# SOM_USB.net
KiCad netlist of a schematic drawn in Altium Designer
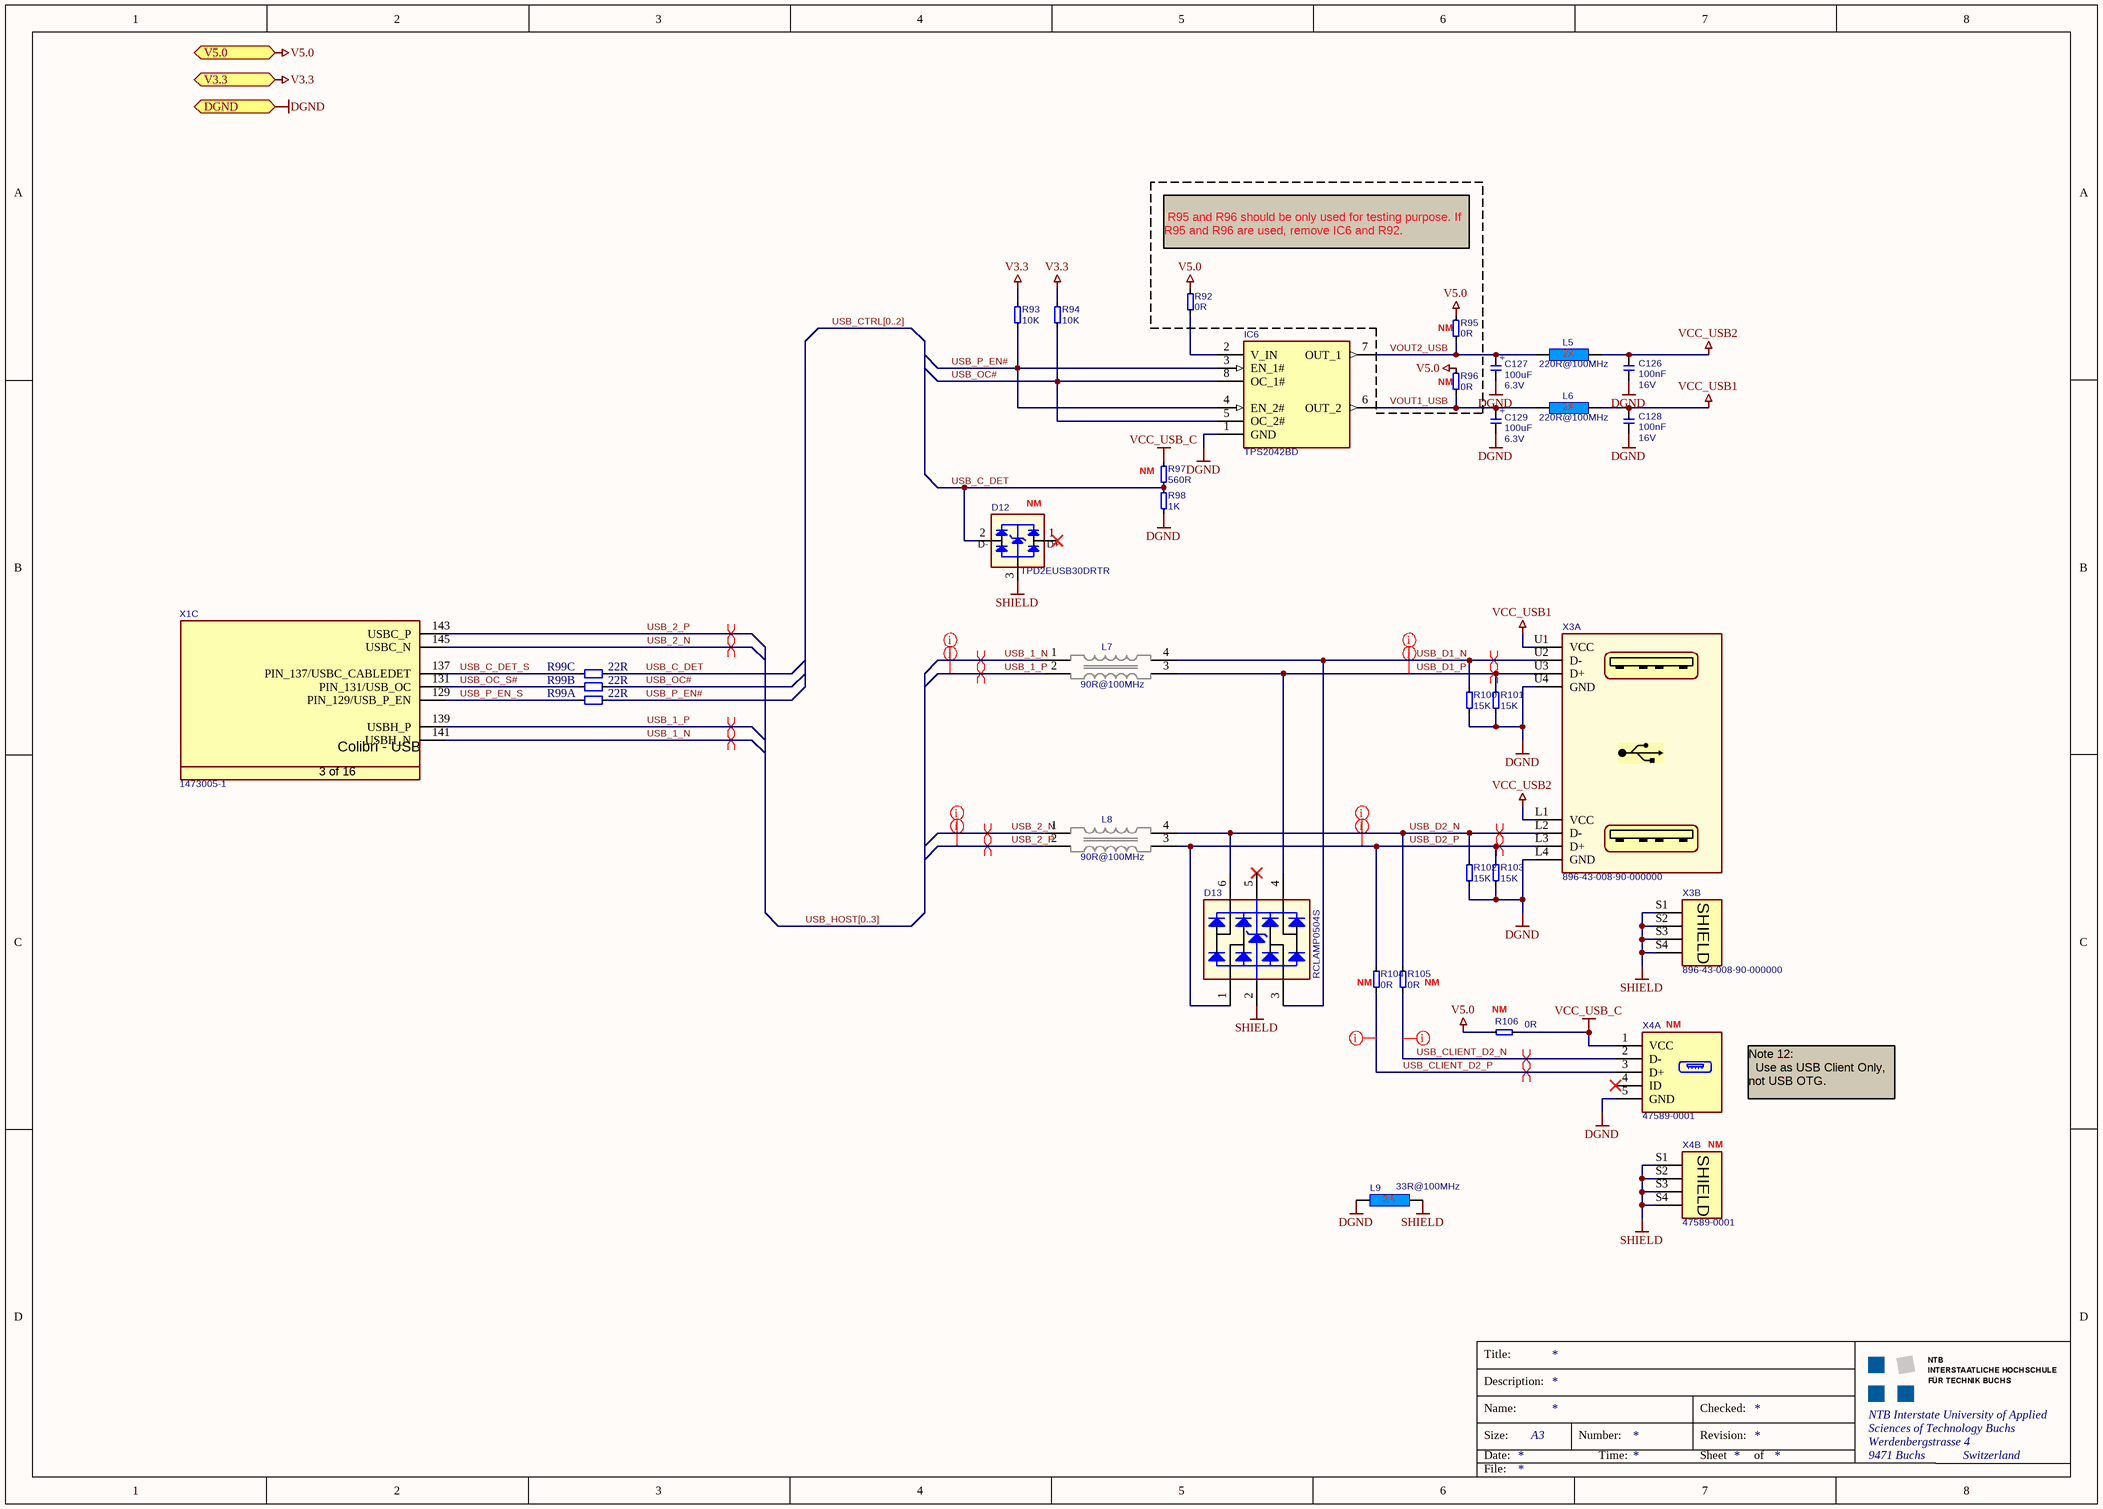
[diagram p0: SOM_USB.SchDoc]

(export (version "E")
  (design (tool "Eeschema 10.0.6"))
  (components
    (comp (ref "C126")
      (value "100nF")
      (footprint "0603_3D")
      (description "Capacitor Ceramic X7R 100nF 16V 10% 0603")
      (fields
        (field (name "TOLERANCE") "10%")
        (field (name "RATING") "16V")
        (field (name "MANUFACTURER") "Generic")
      )
      (libsource (lib "Viola") (part "C-X7R-100nF-16V-10%-0603"))
    )
    (comp (ref "C127")
      (value "100uF")
      (footprint "1206_Pol")
      (description "Capacitor TA 100uF 10V 20% 3528")
      (fields
        (field (name "TOLERANCE") "20%")
        (field (name "RATING") "6.3V")
        (field (name "MANUFACTURER") "Generic")
      )
      (libsource (lib "Viola") (part "C-TA-100uF-10V-20%-3528"))
    )
    (comp (ref "C128")
      (value "100nF")
      (footprint "0603_3D")
      (description "Capacitor Ceramic X7R 100nF 16V 10% 0603")
      (fields
        (field (name "TOLERANCE") "10%")
        (field (name "RATING") "16V")
        (field (name "MANUFACTURER") "Generic")
      )
      (libsource (lib "Viola") (part "C-X7R-100nF-16V-10%-0603"))
    )
    (comp (ref "C129")
      (value "100uF")
      (footprint "1206_Pol")
      (description "Capacitor TA 100uF 10V 20% 3528")
      (fields
        (field (name "TOLERANCE") "20%")
        (field (name "RATING") "6.3V")
        (field (name "MANUFACTURER") "Generic")
      )
      (libsource (lib "Viola") (part "C-TA-100uF-10V-20%-3528"))
    )
    (comp (ref "D12")
      (value "TPD2EUSB30DRTR")
      (footprint "T_TI_TPD2EUSB30DRTR")
      (description "2 Channel Protection for Super Speed USB3.0")
      (fields (field (name "MANUFACTURER") "TI") (field (name "MANUFACTURER PART NUMBER") "TPD2EUSB30DRTR"))
      (libsource (lib "Viola") (part "D-TI-TPD2EUSB30DRTR"))
    )
    (comp (ref "D13")
      (value "RCLAMP0504S")
      (footprint "T_SOT95P285X90-6N")
      (description "TVS Array low cap")
      (fields (field (name "MANUFACTURER") "Semtech") (field (name "MANUFACTURER PART NUMBER") "RCLAMP0504S"))
      (libsource (lib "Viola") (part "D-Semtech-RClamp0504S-ESD-5V-+/-8KV(Contact)-+/-15KV(Air)"))
    )
    (comp (ref "IC6")
      (value "TPS2042BD")
      (footprint "SOIC127P600X173-8N")
      (description "Dual High Side Switch With OC_DET 500mA/CH")
      (fields
        (field (name "MANUFACTURER") "Texas Instruments")
        (field (name "MANUFACTURER PART NUMBER") "TPS2042BD")
      )
      (libsource (lib "Viola") (part "IC-TI-TPS2042BD"))
    )
    (comp (ref "L5")
      (value "220R@100MHz")
      (footprint "0603_3D")
      (description "220R@100MHz 2A EMI FILTER")
      (fields (field (name "TOLERANCE") "25%") (field (name "MANUFACTURER") "Generic"))
      (libsource (lib "Viola") (part "L-220R@100MHz-2A-25%-0603"))
    )
    (comp (ref "L6")
      (value "220R@100MHz")
      (footprint "0603_3D")
      (description "220R@100MHz 2A EMI FILTER")
      (fields (field (name "TOLERANCE") "25%") (field (name "MANUFACTURER") "Generic"))
      (libsource (lib "Viola") (part "L-220R@100MHz-2A-25%-0603"))
    )
    (comp (ref "L7")
      (value "90R@100MHz")
      (footprint "T_Murata_DLW21HN900SQ2")
      (description "Common Mode Choke High Speed 90R 330mA")
      (fields (field (name "TOLERANCE") "25%") (field (name "MANUFACTURER") "Murata"))
      (libsource (lib "Viola") (part "L-Murata-DLW21HN900SQ2-90R@100MHz-330mA-25%"))
    )
    (comp (ref "L8")
      (value "90R@100MHz")
      (footprint "T_Murata_DLW21HN900SQ2")
      (description "Common Mode Choke High Speed 90R 330mA")
      (fields (field (name "TOLERANCE") "25%") (field (name "MANUFACTURER") "Murata"))
      (libsource (lib "Viola") (part "L-Murata-DLW21HN900SQ2-90R@100MHz-330mA-25%"))
    )
    (comp (ref "L9")
      (value "33R@100MHz")
      (footprint "0603_3D")
      (description "33R@100MHz 3A EMI FILTER")
      (fields (field (name "TOLERANCE") "25%") (field (name "MANUFACTURER") "Generic"))
      (libsource (lib "Pathos_Div") (part "L-33R@100MHz-3A-0603"))
    )
    (comp (ref "R92")
      (value "0R")
      (footprint "0603_3D")
      (description "Resistor 0 ohm 63mW 1%1206 Jumper")
      (fields (field (name "TOLERANCE") "1%") (field (name "MANUFACTURER") "Generic"))
      (libsource (lib "Viola") (part "R-0R-63mW-1%-1206"))
    )
    (comp (ref "R93")
      (value "10K")
      (footprint "0603_3D")
      (description "Resistor 10 Kohm 63mW 1% 0603")
      (fields (field (name "TOLERANCE") "1%") (field (name "MANUFACTURER") "Generic"))
      (libsource (lib "Viola") (part "R-10KR-63mW-1%-0603"))
    )
    (comp (ref "R94")
      (value "10K")
      (footprint "0603_3D")
      (description "Resistor 10 Kohm 63mW 1% 0603")
      (fields (field (name "TOLERANCE") "1%") (field (name "MANUFACTURER") "Generic"))
      (libsource (lib "Viola") (part "R-10KR-63mW-1%-0603"))
    )
    (comp (ref "R95")
      (value "0R")
      (footprint "0603_3D")
      (description "Resistor 0 ohm 100mW Jumper 0603")
      (fields (field (name "TOLERANCE") "1%") (field (name "MANUFACTURER") "Generic"))
      (libsource (lib "Viola") (part "R-0R-100mW-JP-0603"))
    )
    (comp (ref "R96")
      (value "0R")
      (footprint "0603_3D")
      (description "Resistor 0 ohm 100mW Jumper 0603")
      (fields (field (name "TOLERANCE") "1%") (field (name "MANUFACTURER") "Generic"))
      (libsource (lib "Viola") (part "R-0R-100mW-JP-0603"))
    )
    (comp (ref "R97")
      (value "560R")
      (footprint "0603_3D")
      (description "Resistor 560 ohm 63mW 5% 0603")
      (fields (field (name "TOLERANCE") "5%") (field (name "MANUFACTURER") "Generic"))
      (libsource (lib "Viola") (part "R-560R-63mW-5%-0603"))
    )
    (comp (ref "R98")
      (value "1K")
      (footprint "0603_3D")
      (description "Resistor 1 Kohm 63mW 5% 0603")
      (fields (field (name "TOLERANCE") "5%") (field (name "MANUFACTURER") "Generic"))
      (libsource (lib "Viola") (part "R-1KR-63mW-5%-0603"))
    )
    (comp (ref "R99")
      (value "22R")
      (footprint "R_Array_CAT16-J4")
      (fields (field (name "Comment") "R Array"))
      (libsource (lib "EFSSensorboard_1") (part "R_Array"))
    )
    (comp (ref "R100")
      (value "15K")
      (footprint "0603_3D")
      (description "Resistor 15 Kohm 63mW 5% 0603")
      (fields (field (name "TOLERANCE") "5%") (field (name "MANUFACTURER") "Generic"))
      (libsource (lib "Viola") (part "R-15KR-63mW-1%-0603"))
    )
    (comp (ref "R101")
      (value "15K")
      (footprint "0603_3D")
      (description "Resistor 15 Kohm 63mW 5% 0603")
      (fields (field (name "TOLERANCE") "5%") (field (name "MANUFACTURER") "Generic"))
      (libsource (lib "Viola") (part "R-15KR-63mW-1%-0603"))
    )
    (comp (ref "R102")
      (value "15K")
      (footprint "0603_3D")
      (description "Resistor 15 Kohm 63mW 5% 0603")
      (fields (field (name "TOLERANCE") "5%") (field (name "MANUFACTURER") "Generic"))
      (libsource (lib "Viola") (part "R-15KR-63mW-1%-0603"))
    )
    (comp (ref "R103")
      (value "15K")
      (footprint "0603_3D")
      (description "Resistor 15 Kohm 63mW 5% 0603")
      (fields (field (name "TOLERANCE") "5%") (field (name "MANUFACTURER") "Generic"))
      (libsource (lib "Viola") (part "R-15KR-63mW-1%-0603"))
    )
    (comp (ref "R104")
      (value "0R")
      (footprint "0603_3D")
      (description "Resistor 0 ohm 100mW Jumper 0603")
      (fields (field (name "TOLERANCE") "1%") (field (name "MANUFACTURER") "Generic"))
      (libsource (lib "Viola") (part "R-0R-100mW-JP-0603"))
    )
    (comp (ref "R105")
      (value "0R")
      (footprint "0603_3D")
      (description "Resistor 0 ohm 100mW Jumper 0603")
      (fields (field (name "TOLERANCE") "1%") (field (name "MANUFACTURER") "Generic"))
      (libsource (lib "Viola") (part "R-0R-100mW-JP-0603"))
    )
    (comp (ref "R106")
      (value "0R")
      (footprint "0603_3D")
      (description "Resistor 0 ohm 100mW Jumper 0603")
      (fields (field (name "TOLERANCE") "1%") (field (name "MANUFACTURER") "Generic"))
      (libsource (lib "Viola") (part "R-0R-100mW-JP-0603"))
    )
    (comp (ref "X1")
      (value "1473005-1")
      (footprint "T_Tyco_1473005-1")
      (description "SODIMM Connector")
      (fields (field (name "MANUFACTURER") "Tyco") (field (name "MANUFACTURER PART NUMBER") "1473005-1"))
      (libsource (lib "Viola") (part "CON-Tyco-1473005-1-200-0.6mm"))
    )
    (comp (ref "X3")
      (value "896-43-008-90-000000")
      (footprint "T_MMMC_896-43-008-90-000000")
      (description "USB 2.0 double row, Type A")
      (fields
        (field (name "MANUFACTURER") "Mill-Max Mfg. Corp.")
        (field (name "MANUFACTURER PART NUMBER") "896-43-008-90-000000")
      )
      (libsource (lib "Viola") (part "CON-MMMC-896-43-008-90-000000"))
    )
    (comp (ref "X4")
      (value "CON-Molex-47589-0001-5-0.65")
      (footprint "T_Molex_47589-0001")
      (description "Micro USB OTG Connector")
      (fields (field (name "MANUFACTURER") "Molex") (field (name "MANUFACTURER PART NUMBER") "47589-0001"))
      (libsource (lib "Viola") (part "CON-Molex-47589-0001-5-0.65"))
    )
  )
  (nets
    (net (code "8") (name "/USB_1_N") (class "Default")
      (node (ref "L7") (pin "1") (pinfunction "1_1") (pintype "passive"))
      (node (ref "X1") (pin "141") (pinfunction "USBH_N_141") (pintype "passive"))
    )
    (net (code "9") (name "/USB_1_P") (class "Default")
      (node (ref "L7") (pin "2") (pinfunction "2_2") (pintype "passive"))
      (node (ref "X1") (pin "139") (pinfunction "USBH_P_139") (pintype "passive"))
    )
    (net (code "10") (name "/USB_2_N") (class "Default")
      (node (ref "L8") (pin "1") (pinfunction "1_1") (pintype "passive"))
      (node (ref "X1") (pin "145") (pinfunction "USBC_N_145") (pintype "passive"))
    )
    (net (code "11") (name "/USB_2_P") (class "Default")
      (node (ref "L8") (pin "2") (pinfunction "2_2") (pintype "passive"))
      (node (ref "X1") (pin "143") (pinfunction "USBC_P_143") (pintype "passive"))
    )
    (net (code "12") (name "/USB_CLIENT_D2_N") (class "Default")
      (node (ref "R105") (pin "1") (pinfunction "1_1") (pintype "passive"))
      (node (ref "X4") (pin "2") (pinfunction "D-_2") (pintype "passive"))
    )
    (net (code "13") (name "/USB_CLIENT_D2_P") (class "Default")
      (node (ref "R104") (pin "1") (pinfunction "1_1") (pintype "passive"))
      (node (ref "X4") (pin "3") (pinfunction "D+_3") (pintype "passive"))
    )
    (net (code "15") (name "/USB_C_DET") (class "Default")
      (node (ref "D12") (pin "2") (pinfunction "D-_2") (pintype "power_in"))
      (node (ref "R97") (pin "1") (pinfunction "1_1") (pintype "passive"))
      (node (ref "R98") (pin "2") (pinfunction "2_2") (pintype "passive"))
      (node (ref "R99") (pin "2C") (pinfunction "2_2C") (pintype "passive"))
    )
    (net (code "16") (name "/USB_C_DET_S") (class "Default")
      (node (ref "R99") (pin "1C") (pinfunction "1_1C") (pintype "passive"))
      (node (ref "X1") (pin "137") (pinfunction "PIN_137/USBC_CABLEDET_137") (pintype "passive"))
    )
    (net (code "17") (name "/USB_D1_N") (class "Default")
      (node (ref "D13") (pin "3") (pinfunction "3_3") (pintype "power_in"))
      (node (ref "L7") (pin "4") (pinfunction "4_4") (pintype "passive"))
      (node (ref "R100") (pin "2") (pinfunction "2_2") (pintype "passive"))
      (node (ref "X3") (pin "U2") (pinfunction "D-_U2") (pintype "passive"))
    )
    (net (code "18") (name "/USB_D1_P") (class "Default")
      (node (ref "D13") (pin "4") (pinfunction "4_4") (pintype "power_in"))
      (node (ref "L7") (pin "3") (pinfunction "3_3") (pintype "passive"))
      (node (ref "R101") (pin "2") (pinfunction "2_2") (pintype "passive"))
      (node (ref "X3") (pin "U3") (pinfunction "D+_U3") (pintype "passive"))
    )
    (net (code "19") (name "/USB_D2_N") (class "Default")
      (node (ref "D13") (pin "6") (pinfunction "6_6") (pintype "power_in"))
      (node (ref "L8") (pin "4") (pinfunction "4_4") (pintype "passive"))
      (node (ref "R102") (pin "2") (pinfunction "2_2") (pintype "passive"))
      (node (ref "R105") (pin "2") (pinfunction "2_2") (pintype "passive"))
      (node (ref "X3") (pin "L2") (pinfunction "D-_L2") (pintype "passive"))
    )
    (net (code "20") (name "/USB_D2_P") (class "Default")
      (node (ref "D13") (pin "1") (pinfunction "1_1") (pintype "power_in"))
      (node (ref "L8") (pin "3") (pinfunction "3_3") (pintype "passive"))
      (node (ref "R103") (pin "2") (pinfunction "2_2") (pintype "passive"))
      (node (ref "R104") (pin "2") (pinfunction "2_2") (pintype "passive"))
      (node (ref "X3") (pin "L3") (pinfunction "D+_L3") (pintype "passive"))
    )
    (net (code "22") (name "/USB_OC#") (class "Default")
      (node (ref "IC6") (pin "5") (pinfunction "OC_2#_5") (pintype "passive"))
      (node (ref "IC6") (pin "8") (pinfunction "OC_1#_8") (pintype "passive"))
      (node (ref "R94") (pin "1") (pinfunction "1_1") (pintype "passive"))
      (node (ref "R99") (pin "2B") (pinfunction "2_2B") (pintype "passive"))
    )
    (net (code "23") (name "/USB_OC_S#") (class "Default")
      (node (ref "R99") (pin "1B") (pinfunction "1_1B") (pintype "passive"))
      (node (ref "X1") (pin "131") (pinfunction "PIN_131/USB_OC_131") (pintype "passive"))
    )
    (net (code "24") (name "/USB_P_EN#") (class "Default")
      (node (ref "IC6") (pin "3") (pinfunction "EN_1#_3") (pintype "input"))
      (node (ref "IC6") (pin "4") (pinfunction "EN_2#_4") (pintype "input"))
      (node (ref "R93") (pin "1") (pinfunction "1_1") (pintype "passive"))
      (node (ref "R99") (pin "2A") (pinfunction "2_2A") (pintype "passive"))
    )
    (net (code "25") (name "/USB_P_EN_S") (class "Default")
      (node (ref "R99") (pin "1A") (pinfunction "1_1A") (pintype "passive"))
      (node (ref "X1") (pin "129") (pinfunction "PIN_129/USB_P_EN_129") (pintype "passive"))
    )
    (net (code "26") (name "/VOUT1_USB") (class "Default")
      (node (ref "C129") (pin "1") (pinfunction "1_1") (pintype "passive"))
      (node (ref "IC6") (pin "6") (pinfunction "OUT_2_6") (pintype "output"))
      (node (ref "L6") (pin "1") (pinfunction "1_1") (pintype "passive"))
      (node (ref "R96") (pin "1") (pinfunction "1_1") (pintype "passive"))
    )
    (net (code "27") (name "/VOUT2_USB") (class "Default")
      (node (ref "C127") (pin "1") (pinfunction "1_1") (pintype "passive"))
      (node (ref "IC6") (pin "7") (pinfunction "OUT_1_7") (pintype "output"))
      (node (ref "L5") (pin "1") (pinfunction "1_1") (pintype "passive"))
      (node (ref "R95") (pin "1") (pinfunction "1_1") (pintype "passive"))
    )
    (net (code "28") (name "DGND") (class "Default")
      (node (ref "C126") (pin "1") (pinfunction "1_1") (pintype "passive"))
      (node (ref "C127") (pin "2") (pinfunction "2_2") (pintype "passive"))
      (node (ref "C128") (pin "1") (pinfunction "1_1") (pintype "passive"))
      (node (ref "C129") (pin "2") (pinfunction "2_2") (pintype "passive"))
      (node (ref "IC6") (pin "1") (pinfunction "GND_1") (pintype "power_in"))
      (node (ref "L9") (pin "1") (pinfunction "1_1") (pintype "passive"))
      (node (ref "R100") (pin "1") (pinfunction "1_1") (pintype "passive"))
      (node (ref "R101") (pin "1") (pinfunction "1_1") (pintype "passive"))
      (node (ref "R102") (pin "1") (pinfunction "1_1") (pintype "passive"))
      (node (ref "R103") (pin "1") (pinfunction "1_1") (pintype "passive"))
      (node (ref "R98") (pin "1") (pinfunction "1_1") (pintype "passive"))
      (node (ref "X3") (pin "L4") (pinfunction "GND_L4") (pintype "power_in"))
      (node (ref "X3") (pin "U4") (pinfunction "GND_U4") (pintype "power_in"))
      (node (ref "X4") (pin "5") (pinfunction "GND_5") (pintype "power_in"))
    )
    (net (code "29") (name "Net-(IC6-V_IN)") (class "Default")
      (node (ref "IC6") (pin "2") (pinfunction "V_IN_2") (pintype "power_in"))
      (node (ref "R92") (pin "1") (pinfunction "1_1") (pintype "passive"))
    )
    (net (code "30") (name "SHIELD") (class "Default")
      (node (ref "D12") (pin "3") (pinfunction "3_3") (pintype "power_in"))
      (node (ref "D13") (pin "2") (pinfunction "2_2") (pintype "power_in"))
      (node (ref "L9") (pin "2") (pinfunction "2_2") (pintype "passive"))
      (node (ref "X3") (pin "S1") (pinfunction "SHIELD_S1") (pintype "passive"))
      (node (ref "X3") (pin "S2") (pinfunction "SHIELD_S2") (pintype "passive"))
      (node (ref "X3") (pin "S3") (pinfunction "SHIELD_S3") (pintype "passive"))
      (node (ref "X3") (pin "S4") (pinfunction "SHIELD_S4") (pintype "passive"))
      (node (ref "X4") (pin "S1") (pinfunction "SHIELD_S1") (pintype "passive"))
      (node (ref "X4") (pin "S2") (pinfunction "SHIELD_S2") (pintype "passive"))
      (node (ref "X4") (pin "S3") (pinfunction "SHIELD_S3") (pintype "passive"))
      (node (ref "X4") (pin "S4") (pinfunction "SHIELD_S4") (pintype "passive"))
    )
    (net (code "31") (name "V3.3") (class "Default")
      (node (ref "R93") (pin "2") (pinfunction "2_2") (pintype "passive"))
      (node (ref "R94") (pin "2") (pinfunction "2_2") (pintype "passive"))
    )
    (net (code "32") (name "V5.0") (class "Default")
      (node (ref "R106") (pin "2") (pinfunction "2_2") (pintype "passive"))
      (node (ref "R92") (pin "2") (pinfunction "2_2") (pintype "passive"))
      (node (ref "R95") (pin "2") (pinfunction "2_2") (pintype "passive"))
      (node (ref "R96") (pin "2") (pinfunction "2_2") (pintype "passive"))
    )
    (net (code "33") (name "VCC_USB1") (class "Default")
      (node (ref "C128") (pin "2") (pinfunction "2_2") (pintype "passive"))
      (node (ref "L6") (pin "2") (pinfunction "2_2") (pintype "passive"))
      (node (ref "X3") (pin "U1") (pinfunction "VCC_U1") (pintype "power_in"))
    )
    (net (code "34") (name "VCC_USB2") (class "Default")
      (node (ref "C126") (pin "2") (pinfunction "2_2") (pintype "passive"))
      (node (ref "L5") (pin "2") (pinfunction "2_2") (pintype "passive"))
      (node (ref "X3") (pin "L1") (pinfunction "VCC_L1") (pintype "power_in"))
    )
    (net (code "35") (name "VCC_USB_C") (class "Default")
      (node (ref "R106") (pin "1") (pinfunction "1_1") (pintype "passive"))
      (node (ref "R97") (pin "2") (pinfunction "2_2") (pintype "passive"))
      (node (ref "X4") (pin "1") (pinfunction "VCC_1") (pintype "power_in"))
    )
    (net (code "36") (name "unconnected-(D12-D+-Pad1)") (class "Default")
      (node (ref "D12") (pin "1") (pinfunction "D+_1") (pintype "power_in+no_connect"))
    )
    (net (code "37") (name "unconnected-(D13-Pad5)") (class "Default")
      (node (ref "D13") (pin "5") (pinfunction "5_5") (pintype "power_in+no_connect"))
    )
    (net (code "38") (name "unconnected-(X4A-ID-Pad4)") (class "Default")
      (node (ref "X4") (pin "4") (pinfunction "ID_4") (pintype "passive+no_connect"))
    )
  )
)
